# ai.net
KiCad netlist of a schematic drawn in Altium Designer
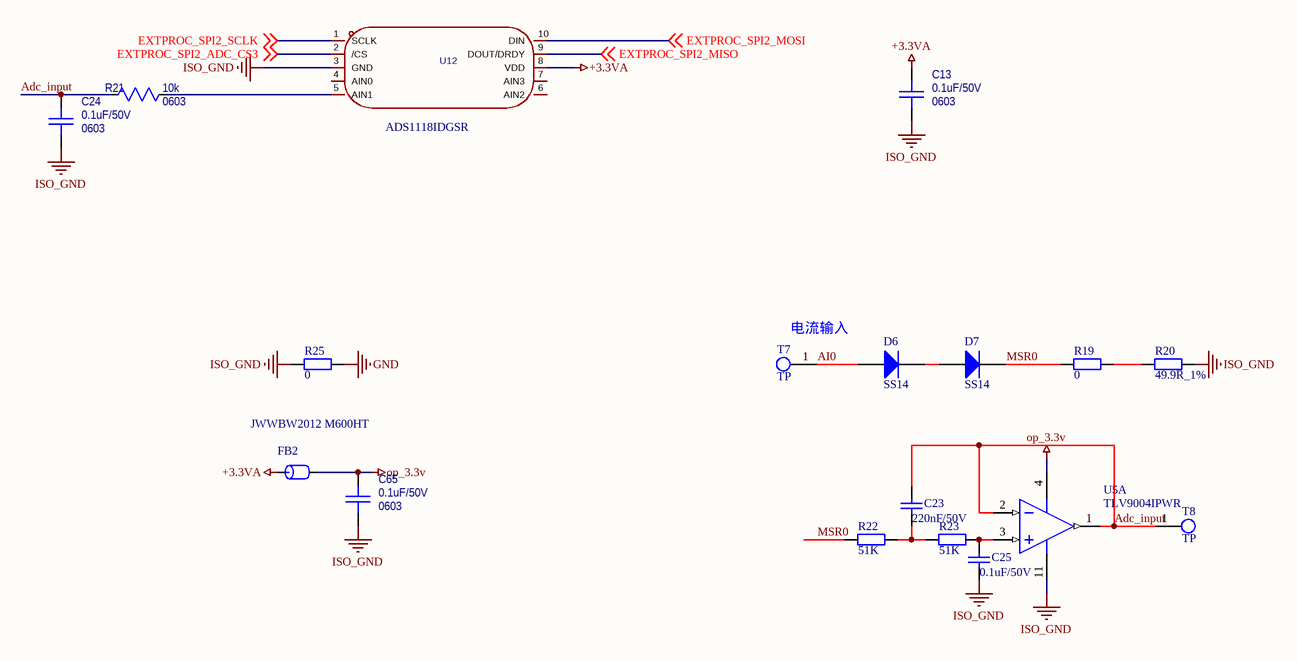
[diagram p0: ai.SchDoc]

(export (version "E")
  (design (tool "Eeschema 10.0.6"))
  (components
    (comp (ref "C13")
      (value "0.1uF/50V")
      (footprint "0603C")
      (description "Capacitor, MLCC")
      (fields (field (name "PACKAGE") "0603"))
      (libsource (lib "Karl") (part "Capacitor_0603"))
    )
    (comp (ref "C23")
      (value "220nF/50V")
      (footprint "0603C")
      (description "Capacitor")
      (libsource (lib "Miscellaneous Devices") (part "Cap"))
    )
    (comp (ref "C24")
      (value "0.1uF/50V")
      (footprint "0603C")
      (description "Capacitor, MLCC")
      (fields (field (name "PACKAGE") "0603"))
      (libsource (lib "Karl") (part "Capacitor_0603"))
    )
    (comp (ref "C25")
      (value "0.1uF/50V")
      (footprint "0603C")
      (description "Capacitor")
      (libsource (lib "Miscellaneous Devices") (part "Cap"))
    )
    (comp (ref "C65")
      (value "0.1uF/50V")
      (footprint "0603C")
      (description "Capacitor, MLCC")
      (fields (field (name "PACKAGE") "0603"))
      (libsource (lib "Karl") (part "Capacitor_0603"))
    )
    (comp (ref "D6")
      (value "SS14")
      (footprint "DO-214AC")
      (description "Default Diode")
      (libsource (lib "Miscellaneous Devices") (part "Diode"))
    )
    (comp (ref "D7")
      (value "SS14")
      (footprint "DO-214AC")
      (description "Default Diode")
      (libsource (lib "Miscellaneous Devices") (part "Diode"))
    )
    (comp (ref "FB2")
      (value "JWWBW2012 M600HT")
      (footprint "0805R")
      (libsource (lib "Schlib_20110825") (part "FB"))
    )
    (comp (ref "R19") (value "0") (footprint "0603R") (libsource (lib "MQlibrary") (part "Res0805M")))
    (comp (ref "R20") (value "49.9R_1%") (footprint "0603R") (libsource (lib "MQlibrary") (part "Res0805M")))
    (comp (ref "R21")
      (value "10k")
      (footprint "0603R")
      (description "Resistor, Standard")
      (fields (field (name "PACKAGE") "0603") (field (name "Comment") "10K/1%"))
      (libsource (lib "Karl") (part "Resistor_0603"))
    )
    (comp (ref "R22") (value "51K") (footprint "0603R") (libsource (lib "MQlibrary") (part "Res0805M")))
    (comp (ref "R23") (value "51K") (footprint "0603R") (libsource (lib "MQlibrary") (part "Res0805M")))
    (comp (ref "R25") (value "0") (footprint "0603R") (libsource (lib "MQlibrary") (part "Res0805M")))
    (comp (ref "T7") (value "TP") (footprint "TPD") (libsource (lib "Schlib_20110825") (part "TP")))
    (comp (ref "T8") (value "TP") (footprint "TPD") (libsource (lib "Schlib_20110825") (part "TP")))
    (comp (ref "U5")
      (value "TLV9004IPWR")
      (footprint "TSSOP14")
      (description "Quad High-speed, Ultra Low-power, Single-Supply TTL comparator")
      (libsource (lib "Maxim Analog Comparator") (part "MAX908EPD"))
    )
    (comp (ref "U12")
      (value "ADS1118IDGSR")
      (footprint "VSSOP-10_L3.0-W3.0-P0.50-LS4.9-BL")
      (libsource (lib "altium-import") (part "root_0_ADS1118IDGSR_C55347_"))
    )
  )
  (nets
    (net (code "1") (name "+3.3VA") (class "Default")
      (node (ref "C13") (pin "1") (pinfunction "1_1") (pintype "passive"))
      (node (ref "FB2") (pin "1") (pintype "passive"))
      (node (ref "U12") (pin "8") (pinfunction "VDD_8") (pintype "passive"))
    )
    (net (code "2") (name "/AI0") (class "Default")
      (node (ref "D6") (pin "1") (pinfunction "A_1") (pintype "passive"))
      (node (ref "T7") (pin "1") (pintype "passive"))
    )
    (net (code "3") (name "/Adc_input") (class "Default")
      (node (ref "C23") (pin "2") (pinfunction "2_2") (pintype "passive"))
      (node (ref "C24") (pin "1") (pinfunction "1_1") (pintype "passive"))
      (node (ref "R21") (pin "2") (pinfunction "2_2") (pintype "passive"))
      (node (ref "T8") (pin "1") (pintype "passive"))
      (node (ref "U5") (pin "1") (pinfunction "OUT_1") (pintype "output"))
      (node (ref "U5") (pin "2") (pinfunction "IN-_2") (pintype "input"))
    )
    (net (code "4") (name "/MSR0") (class "Default")
      (node (ref "D7") (pin "2") (pinfunction "K_2") (pintype "passive"))
      (node (ref "R19") (pin "2") (pinfunction "2_2") (pintype "passive"))
      (node (ref "R22") (pin "2") (pinfunction "2_2") (pintype "passive"))
    )
    (net (code "5") (name "EXTPROC_SPI2_ADC_CS3") (class "Default")
      (node (ref "U12") (pin "2") (pinfunction "/CS_2") (pintype "passive"))
    )
    (net (code "6") (name "EXTPROC_SPI2_MISO") (class "Default")
      (node (ref "U12") (pin "9") (pinfunction "DOUT/DRDY_9") (pintype "passive"))
    )
    (net (code "7") (name "EXTPROC_SPI2_MOSI") (class "Default")
      (node (ref "U12") (pin "10") (pinfunction "DIN_10") (pintype "passive"))
    )
    (net (code "8") (name "EXTPROC_SPI2_SCLK") (class "Default")
      (node (ref "U12") (pin "1") (pinfunction "SCLK_1") (pintype "passive"))
    )
    (net (code "9") (name "GND") (class "Default")
      (node (ref "R25") (pin "1") (pinfunction "1_1") (pintype "passive"))
    )
    (net (code "10") (name "ISO_GND") (class "Default")
      (node (ref "C13") (pin "2") (pinfunction "2_2") (pintype "passive"))
      (node (ref "C24") (pin "2") (pinfunction "2_2") (pintype "passive"))
      (node (ref "C25") (pin "1") (pinfunction "1_1") (pintype "passive"))
      (node (ref "C65") (pin "2") (pinfunction "2_2") (pintype "passive"))
      (node (ref "R20") (pin "1") (pinfunction "1_1") (pintype "passive"))
      (node (ref "R25") (pin "2") (pinfunction "2_2") (pintype "passive"))
      (node (ref "U12") (pin "3") (pinfunction "GND_3") (pintype "passive"))
      (node (ref "U5") (pin "11") (pinfunction "GND_11") (pintype "power_in"))
    )
    (net (code "11") (name "Net-(C23-Pad1)") (class "Default")
      (node (ref "C23") (pin "1") (pinfunction "1_1") (pintype "passive"))
      (node (ref "R22") (pin "1") (pinfunction "1_1") (pintype "passive"))
      (node (ref "R23") (pin "2") (pinfunction "2_2") (pintype "passive"))
    )
    (net (code "12") (name "Net-(D6-K)") (class "Default")
      (node (ref "D6") (pin "2") (pinfunction "K_2") (pintype "passive"))
      (node (ref "D7") (pin "1") (pinfunction "A_1") (pintype "passive"))
    )
    (net (code "13") (name "Net-(R19-Pad1)") (class "Default")
      (node (ref "R19") (pin "1") (pinfunction "1_1") (pintype "passive"))
      (node (ref "R20") (pin "2") (pinfunction "2_2") (pintype "passive"))
    )
    (net (code "14") (name "Net-(U5A-IN+)") (class "Default")
      (node (ref "C25") (pin "2") (pinfunction "2_2") (pintype "passive"))
      (node (ref "R23") (pin "1") (pinfunction "1_1") (pintype "passive"))
      (node (ref "U5") (pin "3") (pinfunction "IN+_3") (pintype "input"))
    )
    (net (code "15") (name "Net-(U12-AIN1)") (class "Default")
      (node (ref "R21") (pin "1") (pinfunction "1_1") (pintype "passive"))
      (node (ref "U12") (pin "5") (pinfunction "AIN1_5") (pintype "passive"))
    )
    (net (code "16") (name "op_3.3v") (class "Default")
      (node (ref "C65") (pin "1") (pinfunction "1_1") (pintype "passive"))
      (node (ref "FB2") (pin "2") (pintype "passive"))
      (node (ref "U5") (pin "4") (pinfunction "V+_4") (pintype "power_in"))
    )
    (net (code "17") (name "unconnected-(U12-AIN0-Pad4)") (class "Default")
      (node (ref "U12") (pin "4") (pinfunction "AIN0_4") (pintype "passive"))
    )
    (net (code "18") (name "unconnected-(U12-AIN2-Pad6)") (class "Default")
      (node (ref "U12") (pin "6") (pinfunction "AIN2_6") (pintype "passive"))
    )
    (net (code "19") (name "unconnected-(U12-AIN3-Pad7)") (class "Default")
      (node (ref "U12") (pin "7") (pinfunction "AIN3_7") (pintype "passive"))
    )
  )
)
